# LEDs.net
KiCad netlist of a schematic drawn in Altium Designer
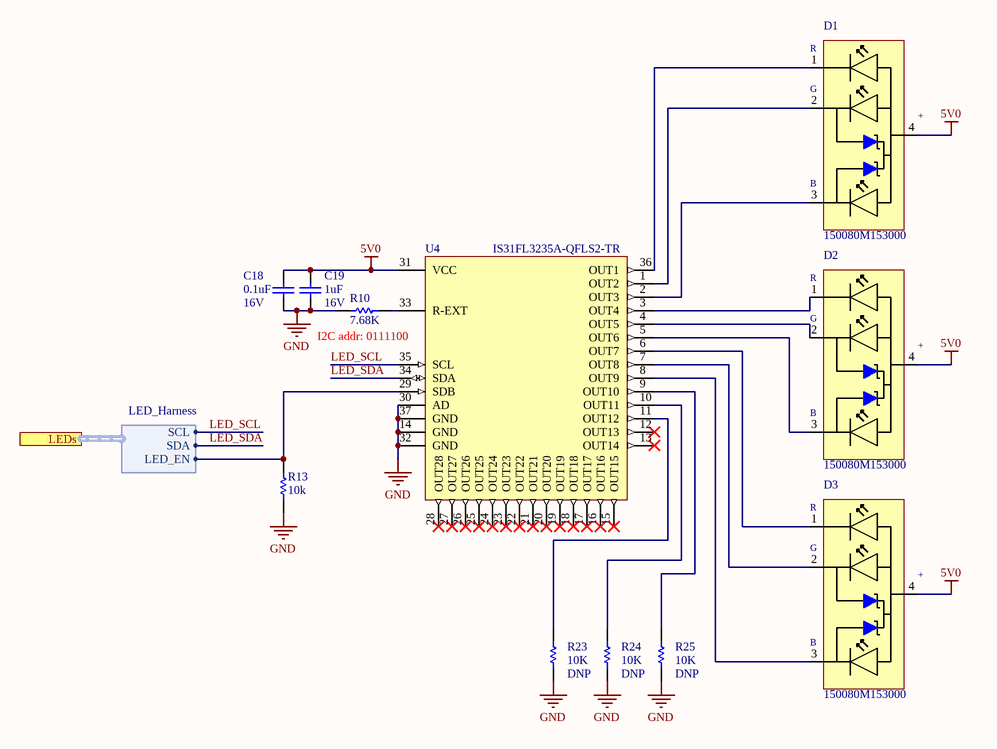
[diagram p0: LEDs.SchDoc]

(export (version "E")
  (design (tool "Eeschema 10.0.6"))
  (components
    (comp (ref "C18")
      (value "0.1uF")
      (footprint "CAPC1005(0402)N")
      (description "CAP CER 0.1UF 16V X5R 0402")
      (fields (field (name "TOLERANCE") "±10%") (field (name "VOLTAGE - RATED") "16V"))
      (libsource (lib "GMLintLib") (part "CAP"))
    )
    (comp (ref "C19")
      (value "1uF")
      (footprint "CAPC1005(0402)N")
      (description "CAP")
      (fields (field (name "TOLERANCE") "±10%") (field (name "VOLTAGE - RATED") "16V"))
      (libsource (lib "GMLintLib") (part "CAP"))
    )
    (comp (ref "D1")
      (value "150080M153000")
      (footprint "*LED_150080M153000")
      (fields (field (name "MF") "Wurth Electronics"))
      (libsource (lib "LegBoard") (part "150080M153000"))
    )
    (comp (ref "D2")
      (value "150080M153000")
      (footprint "*LED_150080M153000")
      (fields (field (name "MF") "Wurth Electronics"))
      (libsource (lib "LegBoard") (part "150080M153000"))
    )
    (comp (ref "D3")
      (value "150080M153000")
      (footprint "*LED_150080M153000")
      (fields (field (name "MF") "Wurth Electronics"))
      (libsource (lib "LegBoard") (part "150080M153000"))
    )
    (comp (ref "R10")
      (value "7.68K")
      (footprint "RESC1005(0402)N")
      (description "Resistor, Chip")
      (libsource (lib "xo-190216") (part "RES"))
    )
    (comp (ref "R13")
      (value "10k")
      (footprint "RESC1005(0402)N")
      (description "Resistor, Chip")
      (libsource (lib "GMLintLib") (part "RES"))
    )
    (comp (ref "R23")
      (value "10K")
      (footprint "0402")
      (description "Resistor")
      (fields
        (field (name "DNP") "DNP")
        (field (name "Comment") "Res1")
        (field (name "PUBLISHER") "Altium Limited")
      )
      (libsource (lib "Miscellaneous Devices") (part "Res1"))
    )
    (comp (ref "R24")
      (value "10K")
      (footprint "0402")
      (description "Resistor")
      (fields
        (field (name "DNP") "DNP")
        (field (name "Comment") "Res1")
        (field (name "PUBLISHER") "Altium Limited")
      )
      (libsource (lib "Miscellaneous Devices") (part "Res1"))
    )
    (comp (ref "R25")
      (value "10K")
      (footprint "0402")
      (description "Resistor")
      (fields
        (field (name "DNP") "DNP")
        (field (name "Comment") "Res1")
        (field (name "PUBLISHER") "Altium Limited")
      )
      (libsource (lib "Miscellaneous Devices") (part "Res1"))
    )
    (comp (ref "U4")
      (value "IS31FL3235A-QFLS2-TR")
      (footprint "QFN40P400X400X80_HS-37N")
      (description "28 channel LED Driver")
      (libsource (lib "billy_misc") (part "IS31FL3235A-QFLS2-TR"))
    )
  )
  (nets
    (net (code "2") (name "/LED_SCL") (class "Default")
      (node (ref "U4") (pin "35") (pinfunction "SCL_35") (pintype "input"))
    )
    (net (code "3") (name "/LED_SDA") (class "Default")
      (node (ref "U4") (pin "34") (pinfunction "SDA_34") (pintype "bidirectional"))
    )
    (net (code "5") (name "5V0") (class "Default")
      (node (ref "C18") (pin "2") (pinfunction "2_2") (pintype "passive"))
      (node (ref "C19") (pin "2") (pinfunction "2_2") (pintype "passive"))
      (node (ref "D1") (pin "4") (pinfunction "A_4") (pintype "passive"))
      (node (ref "D2") (pin "4") (pinfunction "A_4") (pintype "passive"))
      (node (ref "D3") (pin "4") (pinfunction "A_4") (pintype "passive"))
      (node (ref "U4") (pin "31") (pinfunction "VCC_31") (pintype "power_in"))
    )
    (net (code "6") (name "GND") (class "Default")
      (node (ref "C18") (pin "1") (pinfunction "1_1") (pintype "passive"))
      (node (ref "C19") (pin "1") (pinfunction "1_1") (pintype "passive"))
      (node (ref "R10") (pin "1") (pinfunction "1_1") (pintype "passive"))
      (node (ref "R13") (pin "1") (pinfunction "1_1") (pintype "passive"))
      (node (ref "R23") (pin "1") (pinfunction "1_1") (pintype "passive"))
      (node (ref "R24") (pin "1") (pinfunction "1_1") (pintype "passive"))
      (node (ref "R25") (pin "1") (pinfunction "1_1") (pintype "passive"))
      (node (ref "U4") (pin "14") (pinfunction "GND_14") (pintype "power_in"))
      (node (ref "U4") (pin "30") (pinfunction "AD_30") (pintype "passive"))
      (node (ref "U4") (pin "32") (pinfunction "GND_32") (pintype "power_in"))
      (node (ref "U4") (pin "37") (pinfunction "GND_37") (pintype "passive"))
    )
    (net (code "7") (name "Net-(D1-B)") (class "Default")
      (node (ref "D1") (pin "3") (pinfunction "B_3") (pintype "passive"))
      (node (ref "U4") (pin "2") (pinfunction "OUT3_2") (pintype "output"))
    )
    (net (code "8") (name "Net-(D1-G)") (class "Default")
      (node (ref "D1") (pin "2") (pinfunction "G_2") (pintype "passive"))
      (node (ref "U4") (pin "1") (pinfunction "OUT2_1") (pintype "output"))
    )
    (net (code "9") (name "Net-(D1-R)") (class "Default")
      (node (ref "D1") (pin "1") (pinfunction "R_1") (pintype "passive"))
      (node (ref "U4") (pin "36") (pinfunction "OUT1_36") (pintype "output"))
    )
    (net (code "10") (name "Net-(D2-B)") (class "Default")
      (node (ref "D2") (pin "3") (pinfunction "B_3") (pintype "passive"))
      (node (ref "U4") (pin "5") (pinfunction "OUT6_5") (pintype "output"))
    )
    (net (code "11") (name "Net-(D2-G)") (class "Default")
      (node (ref "D2") (pin "2") (pinfunction "G_2") (pintype "passive"))
      (node (ref "U4") (pin "4") (pinfunction "OUT5_4") (pintype "output"))
    )
    (net (code "12") (name "Net-(D2-R)") (class "Default")
      (node (ref "D2") (pin "1") (pinfunction "R_1") (pintype "passive"))
      (node (ref "U4") (pin "3") (pinfunction "OUT4_3") (pintype "output"))
    )
    (net (code "13") (name "Net-(D3-B)") (class "Default")
      (node (ref "D3") (pin "3") (pinfunction "B_3") (pintype "passive"))
      (node (ref "U4") (pin "8") (pinfunction "OUT9_8") (pintype "output"))
    )
    (net (code "14") (name "Net-(D3-G)") (class "Default")
      (node (ref "D3") (pin "2") (pinfunction "G_2") (pintype "passive"))
      (node (ref "U4") (pin "7") (pinfunction "OUT8_7") (pintype "output"))
    )
    (net (code "15") (name "Net-(D3-R)") (class "Default")
      (node (ref "D3") (pin "1") (pinfunction "R_1") (pintype "passive"))
      (node (ref "U4") (pin "6") (pinfunction "OUT7_6") (pintype "output"))
    )
    (net (code "16") (name "Net-(U4-OUT10)") (class "Default")
      (node (ref "R25") (pin "2") (pinfunction "2_2") (pintype "passive"))
      (node (ref "U4") (pin "9") (pinfunction "OUT10_9") (pintype "output"))
    )
    (net (code "17") (name "Net-(U4-OUT11)") (class "Default")
      (node (ref "R24") (pin "2") (pinfunction "2_2") (pintype "passive"))
      (node (ref "U4") (pin "10") (pinfunction "OUT11_10") (pintype "output"))
    )
    (net (code "18") (name "Net-(U4-OUT12)") (class "Default")
      (node (ref "R23") (pin "2") (pinfunction "2_2") (pintype "passive"))
      (node (ref "U4") (pin "11") (pinfunction "OUT12_11") (pintype "output"))
    )
    (net (code "19") (name "Net-(U4-R-EXT)") (class "Default")
      (node (ref "R10") (pin "2") (pinfunction "2_2") (pintype "passive"))
      (node (ref "U4") (pin "33") (pinfunction "R-EXT_33") (pintype "passive"))
    )
    (net (code "20") (name "Net-(U4-SDB)") (class "Default")
      (node (ref "R13") (pin "2") (pinfunction "2_2") (pintype "passive"))
      (node (ref "U4") (pin "29") (pinfunction "SDB_29") (pintype "input"))
    )
    (net (code "21") (name "unconnected-(U4-OUT13-Pad12)") (class "Default")
      (node (ref "U4") (pin "12") (pinfunction "OUT13_12") (pintype "output+no_connect"))
    )
    (net (code "22") (name "unconnected-(U4-OUT14-Pad13)") (class "Default")
      (node (ref "U4") (pin "13") (pinfunction "OUT14_13") (pintype "output+no_connect"))
    )
    (net (code "23") (name "unconnected-(U4-OUT15-Pad15)") (class "Default")
      (node (ref "U4") (pin "15") (pinfunction "OUT15_15") (pintype "output+no_connect"))
    )
    (net (code "24") (name "unconnected-(U4-OUT16-Pad16)") (class "Default")
      (node (ref "U4") (pin "16") (pinfunction "OUT16_16") (pintype "output+no_connect"))
    )
    (net (code "25") (name "unconnected-(U4-OUT17-Pad17)") (class "Default")
      (node (ref "U4") (pin "17") (pinfunction "OUT17_17") (pintype "output+no_connect"))
    )
    (net (code "26") (name "unconnected-(U4-OUT18-Pad18)") (class "Default")
      (node (ref "U4") (pin "18") (pinfunction "OUT18_18") (pintype "output+no_connect"))
    )
    (net (code "27") (name "unconnected-(U4-OUT19-Pad19)") (class "Default")
      (node (ref "U4") (pin "19") (pinfunction "OUT19_19") (pintype "output+no_connect"))
    )
    (net (code "28") (name "unconnected-(U4-OUT20-Pad20)") (class "Default")
      (node (ref "U4") (pin "20") (pinfunction "OUT20_20") (pintype "output+no_connect"))
    )
    (net (code "29") (name "unconnected-(U4-OUT21-Pad21)") (class "Default")
      (node (ref "U4") (pin "21") (pinfunction "OUT21_21") (pintype "output+no_connect"))
    )
    (net (code "30") (name "unconnected-(U4-OUT22-Pad22)") (class "Default")
      (node (ref "U4") (pin "22") (pinfunction "OUT22_22") (pintype "output+no_connect"))
    )
    (net (code "31") (name "unconnected-(U4-OUT23-Pad23)") (class "Default")
      (node (ref "U4") (pin "23") (pinfunction "OUT23_23") (pintype "output+no_connect"))
    )
    (net (code "32") (name "unconnected-(U4-OUT24-Pad24)") (class "Default")
      (node (ref "U4") (pin "24") (pinfunction "OUT24_24") (pintype "output+no_connect"))
    )
    (net (code "33") (name "unconnected-(U4-OUT25-Pad25)") (class "Default")
      (node (ref "U4") (pin "25") (pinfunction "OUT25_25") (pintype "output+no_connect"))
    )
    (net (code "34") (name "unconnected-(U4-OUT26-Pad26)") (class "Default")
      (node (ref "U4") (pin "26") (pinfunction "OUT26_26") (pintype "output+no_connect"))
    )
    (net (code "35") (name "unconnected-(U4-OUT27-Pad27)") (class "Default")
      (node (ref "U4") (pin "27") (pinfunction "OUT27_27") (pintype "output+no_connect"))
    )
    (net (code "36") (name "unconnected-(U4-OUT28-Pad28)") (class "Default")
      (node (ref "U4") (pin "28") (pinfunction "OUT28_28") (pintype "output+no_connect"))
    )
  )
)
